# LDv6_1_TOP.net
KiCad netlist of a schematic drawn in Altium Designer
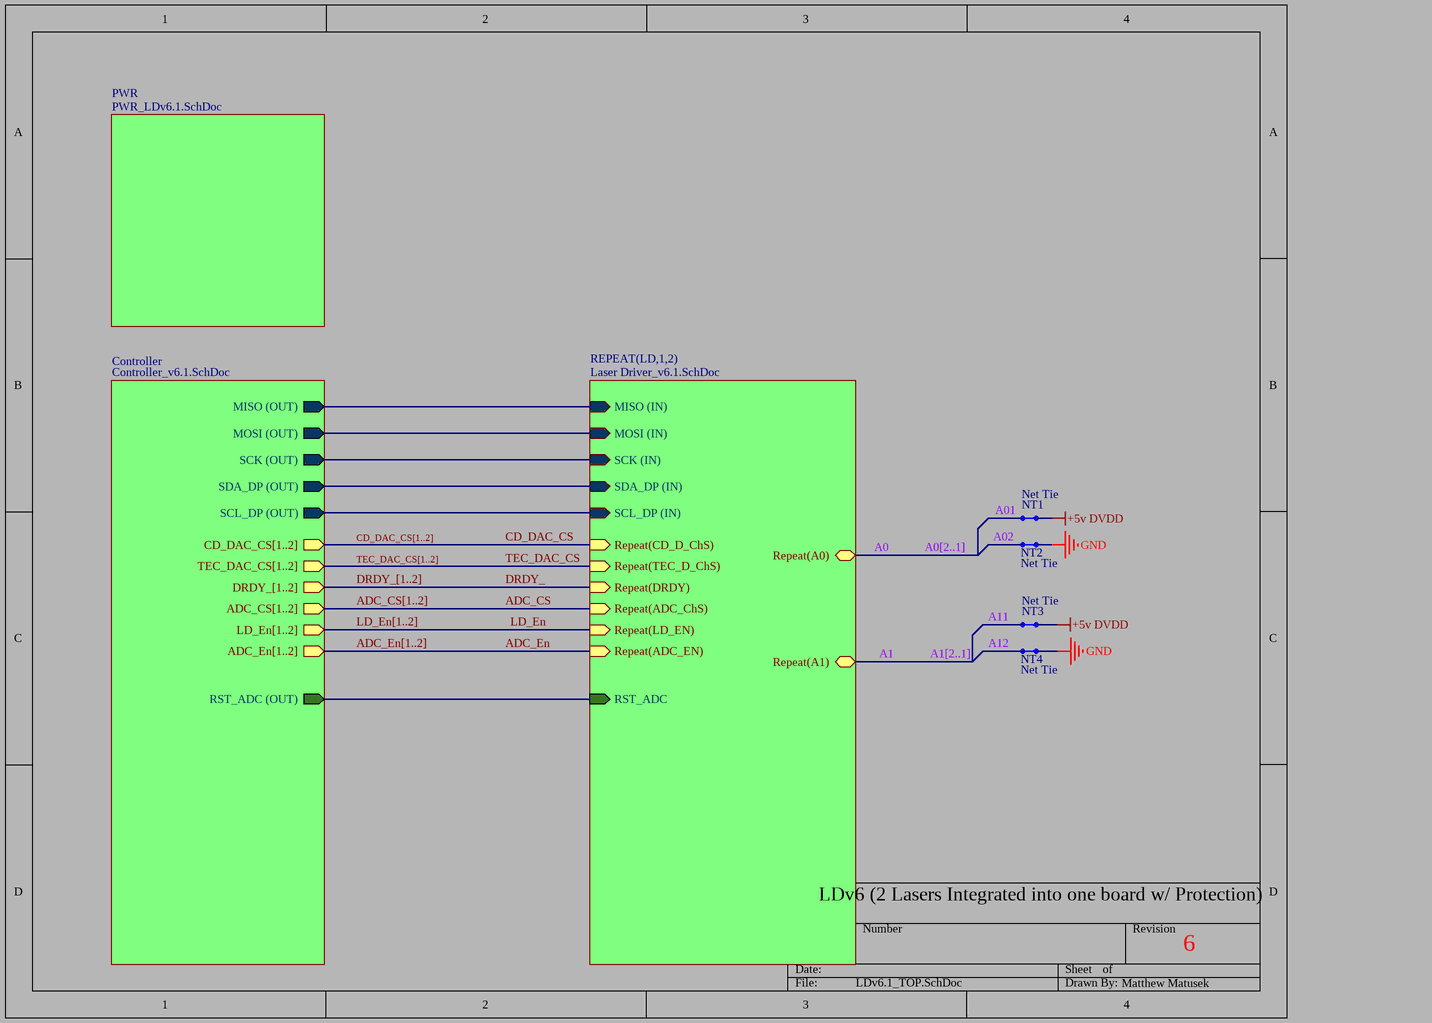
[diagram p0: LDv6.1_TOP.SchDoc]

(export (version "E")
  (design (tool "Eeschema 10.0.6"))
  (components
    (comp (ref "NT1")
      (value "Net Tie")
      (footprint "Net Tie")
      (libsource (lib "FullyLibrary_symbols") (part "Net Tie"))
    )
    (comp (ref "NT2")
      (value "Net Tie")
      (footprint "Net Tie")
      (libsource (lib "FullyLibrary_symbols") (part "Net Tie"))
    )
    (comp (ref "NT3")
      (value "Net Tie")
      (footprint "Net Tie")
      (libsource (lib "FullyLibrary_symbols") (part "Net Tie"))
    )
    (comp (ref "NT4")
      (value "Net Tie")
      (footprint "Net Tie")
      (libsource (lib "FullyLibrary_symbols") (part "Net Tie"))
    )
  )
  (nets
    (net (code "13") (name "+5v DVDD") (class "Default")
      (node (ref "NT1") (pin "2") (pinfunction "2_2") (pintype "passive"))
      (node (ref "NT3") (pin "2") (pinfunction "2_2") (pintype "passive"))
    )
    (net (code "16") (name "/A01") (class "Default")
      (node (ref "NT1") (pin "1") (pinfunction "1_1") (pintype "passive"))
    )
    (net (code "19") (name "/A02") (class "Default")
      (node (ref "NT2") (pin "1") (pinfunction "1_1") (pintype "passive"))
    )
    (net (code "20") (name "/A11") (class "Default")
      (node (ref "NT3") (pin "1") (pinfunction "1_1") (pintype "passive"))
    )
    (net (code "21") (name "/A12") (class "Default")
      (node (ref "NT4") (pin "1") (pinfunction "1_1") (pintype "passive"))
    )
    (net (code "40") (name "GND") (class "Default")
      (node (ref "NT2") (pin "2") (pinfunction "2_2") (pintype "passive"))
      (node (ref "NT4") (pin "2") (pinfunction "2_2") (pintype "passive"))
    )
  )
)
